# Smartcar.net
KiCad netlist of a schematic drawn in Altium Designer
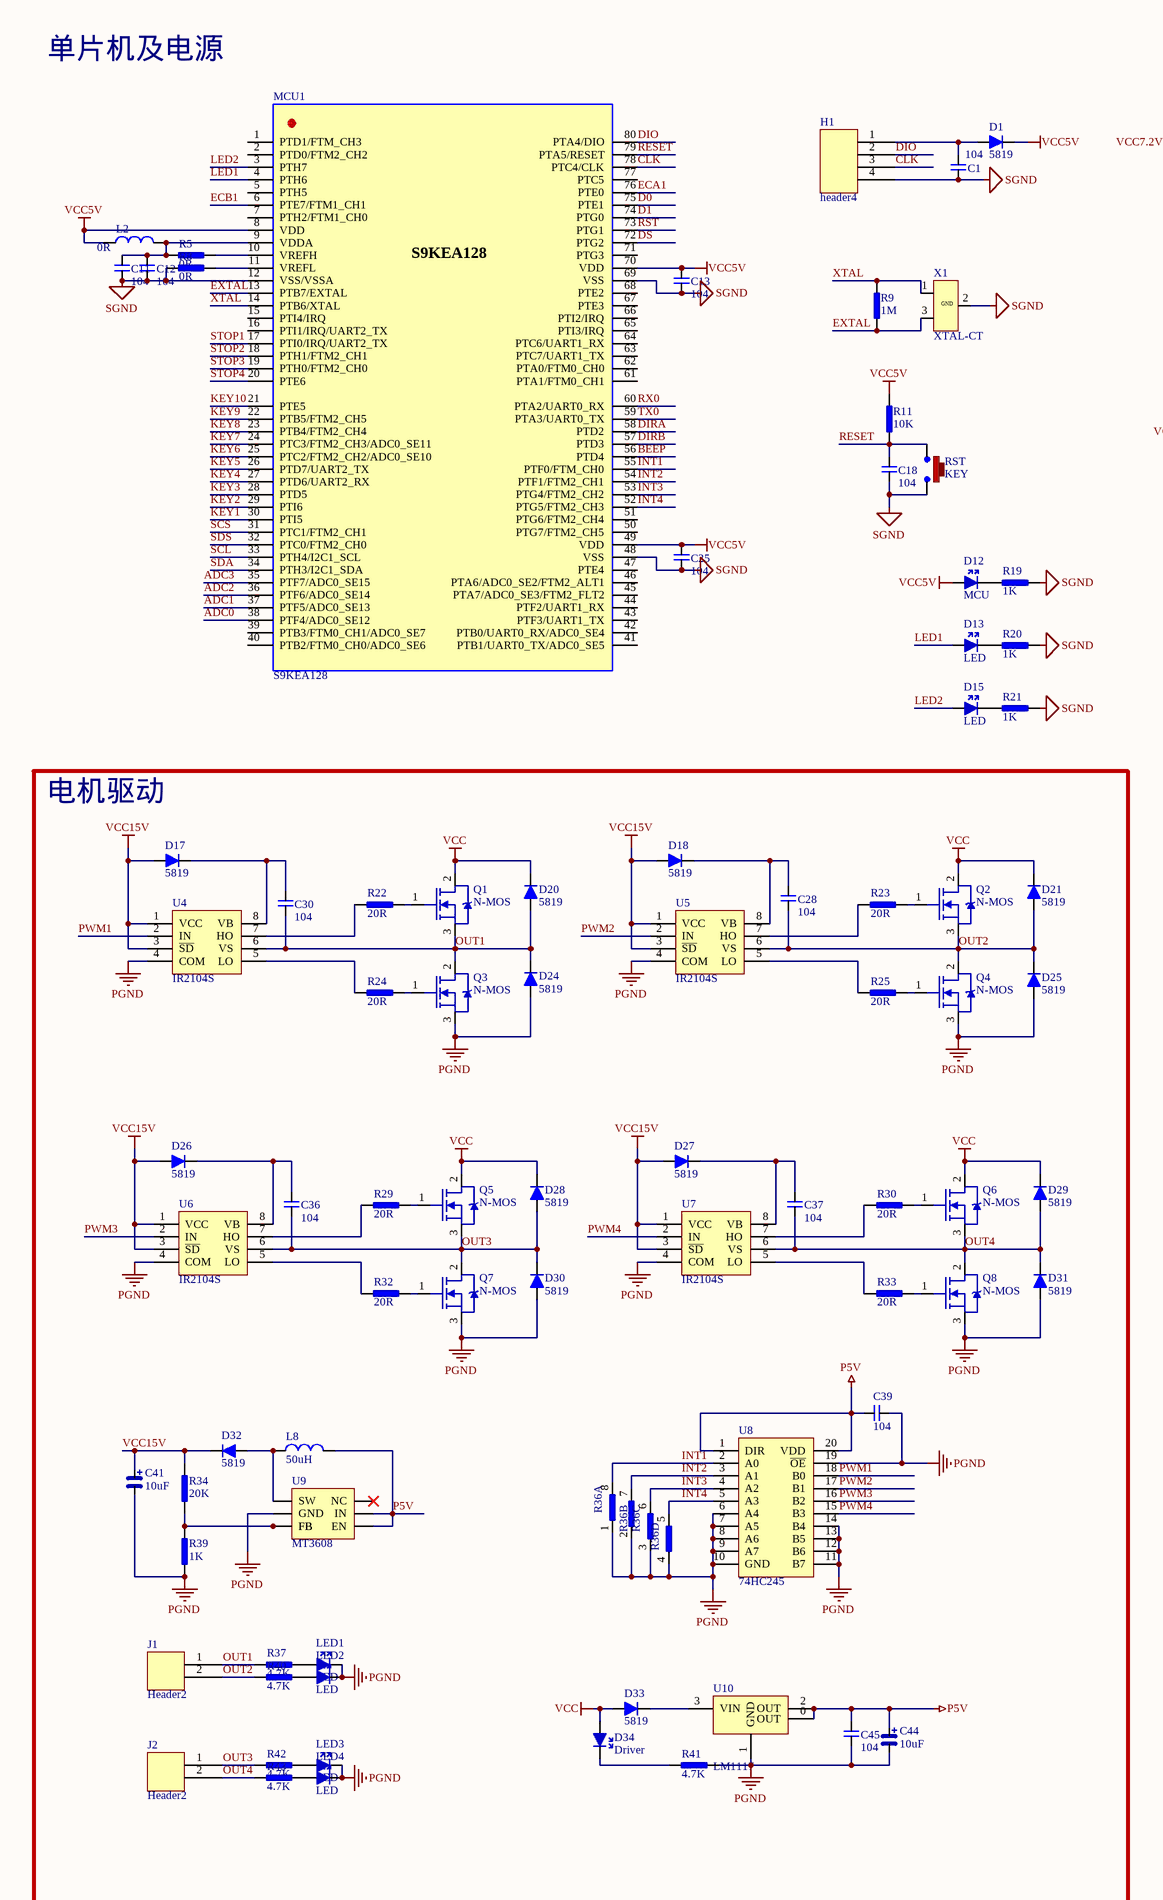
[diagram p0: Smartcar.SchDoc, left]
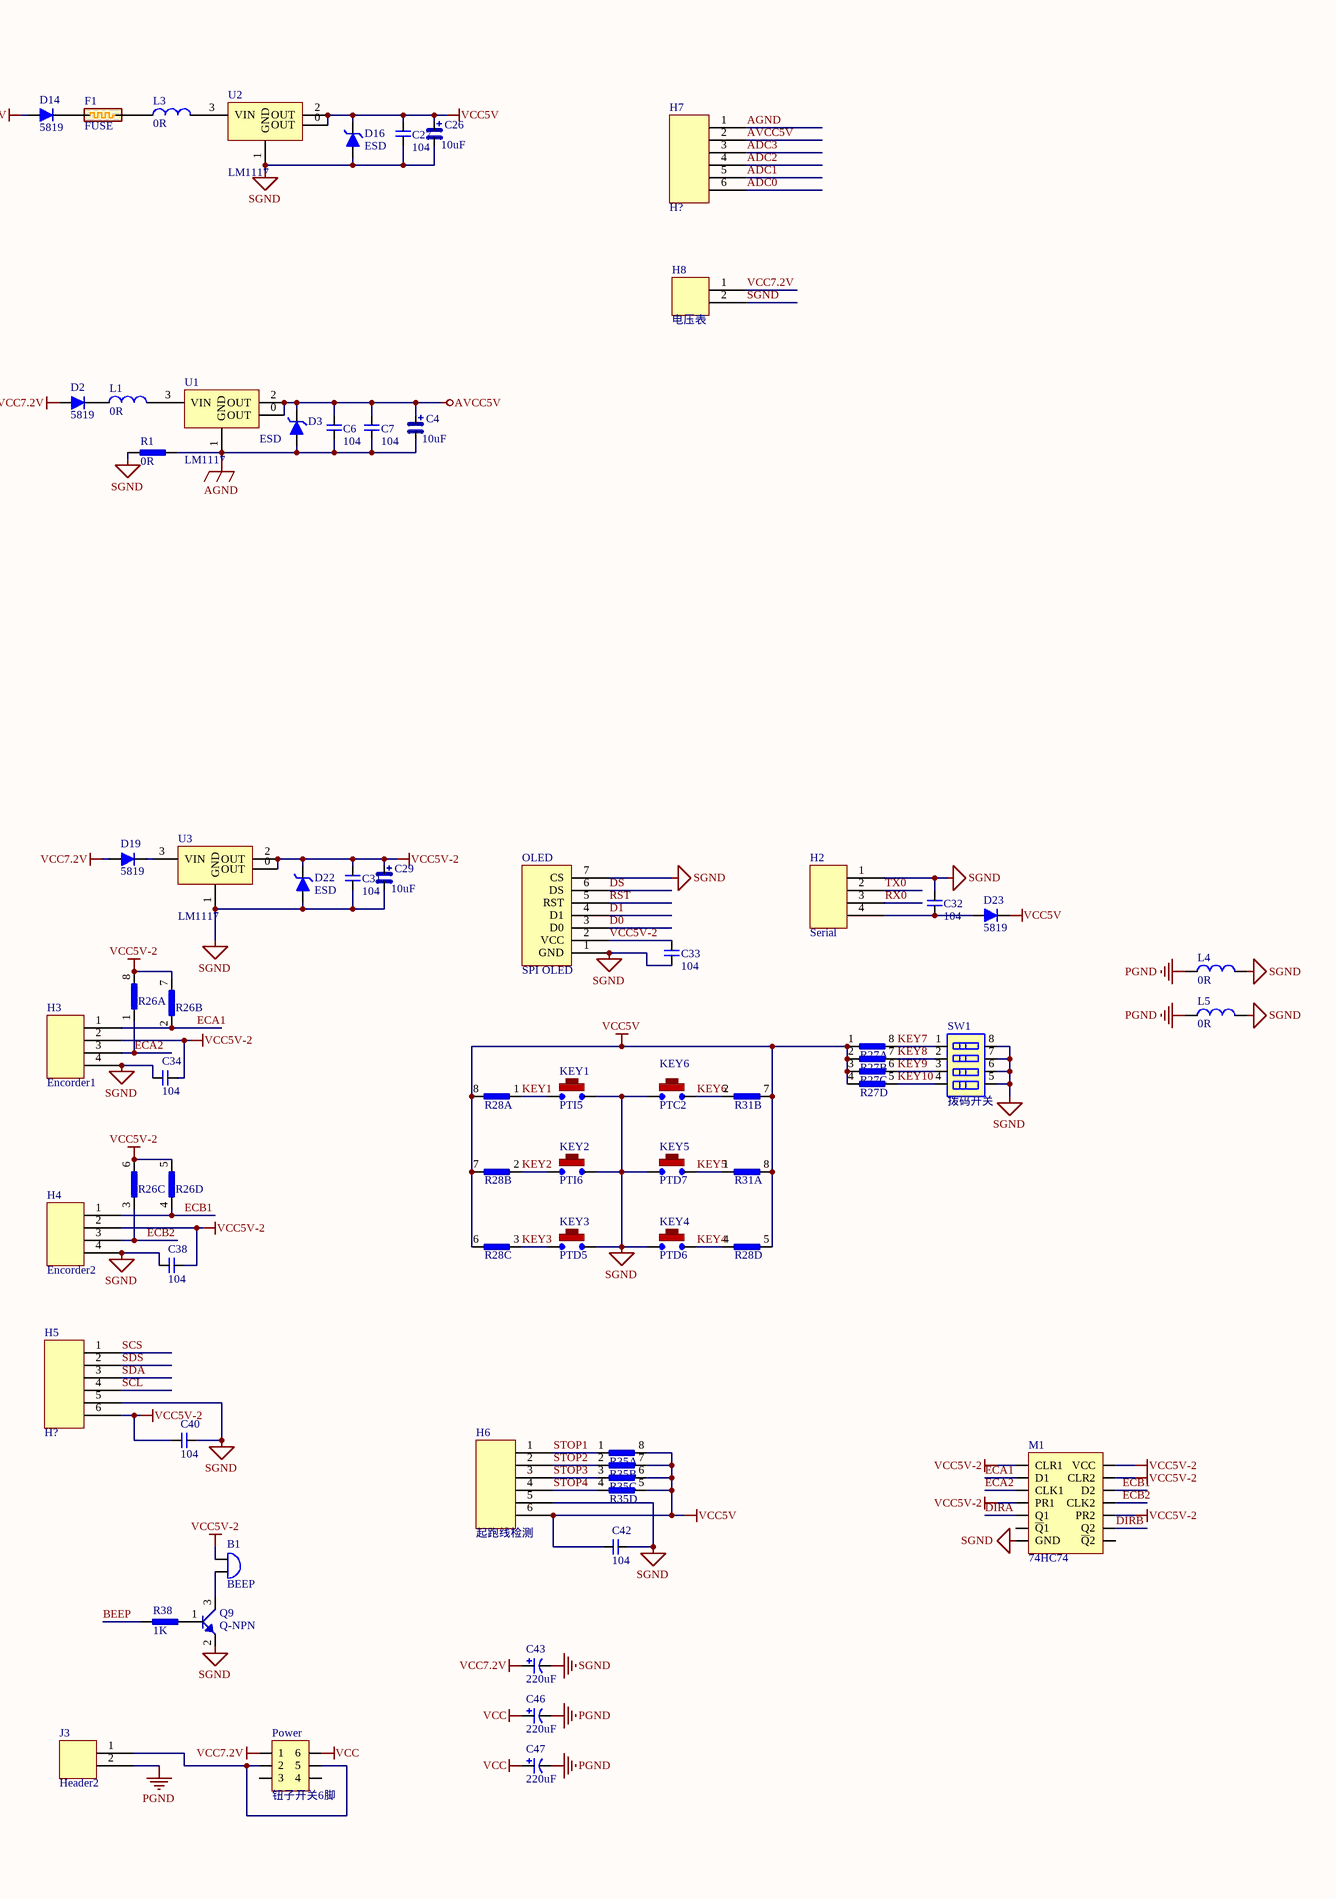
[diagram p1: Smartcar.SchDoc, right]

(export (version "E")
  (design (tool "Eeschema 10.0.6"))
  (components
    (comp (ref "B1") (value "BEEP") (footprint "BEEP") (libsource (lib "常用原理图库") (part "BEEP")))
    (comp (ref "C1") (value "104") (footprint "C0603") (libsource (lib "常用原理图库") (part "CAP")))
    (comp (ref "C4") (value "10uF") (footprint "TAN 3215") (libsource (lib "常用原理图库") (part "C-TAN")))
    (comp (ref "C6") (value "104") (footprint "C0603") (libsource (lib "常用原理图库") (part "CAP")))
    (comp (ref "C7") (value "104") (footprint "C0603") (libsource (lib "常用原理图库") (part "CAP")))
    (comp (ref "C11") (value "104") (footprint "C0603") (libsource (lib "常用原理图库") (part "CAP")))
    (comp (ref "C12") (value "104") (footprint "C0603") (libsource (lib "常用原理图库") (part "CAP")))
    (comp (ref "C13") (value "104") (footprint "C0603") (libsource (lib "常用原理图库") (part "CAP")))
    (comp (ref "C18") (value "104") (footprint "C0603") (libsource (lib "常用原理图库") (part "CAP")))
    (comp (ref "C25") (value "104") (footprint "C0603") (libsource (lib "常用原理图库") (part "CAP")))
    (comp (ref "C26") (value "10uF") (footprint "TAN 3215") (libsource (lib "常用原理图库") (part "C-TAN")))
    (comp (ref "C27") (value "104") (footprint "C0603") (libsource (lib "常用原理图库") (part "CAP")))
    (comp (ref "C28") (value "104") (footprint "C0603") (libsource (lib "常用原理图库") (part "CAP")))
    (comp (ref "C29") (value "10uF") (footprint "TAN 3215") (libsource (lib "常用原理图库") (part "C-TAN")))
    (comp (ref "C30") (value "104") (footprint "C0603") (libsource (lib "常用原理图库") (part "CAP")))
    (comp (ref "C31") (value "104") (footprint "C0603") (libsource (lib "常用原理图库") (part "CAP")))
    (comp (ref "C32") (value "104") (footprint "C0603") (libsource (lib "常用原理图库") (part "CAP")))
    (comp (ref "C33") (value "104") (footprint "C0603") (libsource (lib "常用原理图库") (part "CAP")))
    (comp (ref "C34") (value "104") (footprint "C0603") (libsource (lib "常用原理图库") (part "CAP")))
    (comp (ref "C36") (value "104") (footprint "C0603") (libsource (lib "常用原理图库") (part "CAP")))
    (comp (ref "C37") (value "104") (footprint "C0603") (libsource (lib "常用原理图库") (part "CAP")))
    (comp (ref "C38") (value "104") (footprint "C0603") (libsource (lib "常用原理图库") (part "CAP")))
    (comp (ref "C39") (value "104") (footprint "C0603") (libsource (lib "常用原理图库") (part "CAP")))
    (comp (ref "C40") (value "104") (footprint "C0603") (libsource (lib "常用原理图库") (part "CAP")))
    (comp (ref "C41") (value "10uF") (footprint "TAN 3215") (libsource (lib "常用原理图库") (part "C-TAN")))
    (comp (ref "C42") (value "104") (footprint "C0603") (libsource (lib "常用原理图库") (part "CAP")))
    (comp (ref "C43") (value "220uF") (footprint "CAP6.6X6.6") (libsource (lib "常用原理图库") (part "CAP-SMD")))
    (comp (ref "C44") (value "10uF") (footprint "TAN 3215") (libsource (lib "常用原理图库") (part "C-TAN")))
    (comp (ref "C45") (value "104") (footprint "C0603") (libsource (lib "常用原理图库") (part "CAP")))
    (comp (ref "C46") (value "220uF") (footprint "CAP6.6X6.6") (libsource (lib "常用原理图库") (part "CAP-SMD")))
    (comp (ref "C47") (value "220uF") (footprint "CAP6.6X6.6") (libsource (lib "常用原理图库") (part "CAP-SMD")))
    (comp (ref "D1") (value "5819") (footprint "SOD123") (libsource (lib "常用原理图库") (part "diode")))
    (comp (ref "D2") (value "5819") (footprint "SOD123") (libsource (lib "常用原理图库") (part "diode")))
    (comp (ref "D3") (value "ESD") (footprint "SOD323") (libsource (lib "常用原理图库") (part "D-ESD")))
    (comp (ref "D12") (value "MCU") (footprint "0603LED") (libsource (lib "常用原理图库") (part "LED")))
    (comp (ref "D13") (value "LED") (footprint "0603LED") (libsource (lib "常用原理图库") (part "LED")))
    (comp (ref "D14") (value "5819") (footprint "SOD123") (libsource (lib "常用原理图库") (part "diode")))
    (comp (ref "D15") (value "LED") (footprint "0603LED") (libsource (lib "常用原理图库") (part "LED")))
    (comp (ref "D16") (value "ESD") (footprint "SOD323") (libsource (lib "常用原理图库") (part "D-ESD")))
    (comp (ref "D17") (value "5819") (footprint "SOD123") (libsource (lib "常用原理图库") (part "Diode")))
    (comp (ref "D18") (value "5819") (footprint "SOD123") (libsource (lib "常用原理图库") (part "Diode")))
    (comp (ref "D19") (value "5819") (footprint "SOD123") (libsource (lib "常用原理图库") (part "diode")))
    (comp (ref "D20") (value "5819") (footprint "SOD123") (libsource (lib "常用原理图库") (part "Diode")))
    (comp (ref "D21") (value "5819") (footprint "SOD123") (libsource (lib "常用原理图库") (part "Diode")))
    (comp (ref "D22") (value "ESD") (footprint "SOD323") (libsource (lib "常用原理图库") (part "D-ESD")))
    (comp (ref "D23") (value "5819") (footprint "SOD323") (libsource (lib "常用原理图库") (part "Diode")))
    (comp (ref "D24") (value "5819") (footprint "SOD123") (libsource (lib "常用原理图库") (part "Diode")))
    (comp (ref "D25") (value "5819") (footprint "SOD123") (libsource (lib "常用原理图库") (part "Diode")))
    (comp (ref "D26") (value "5819") (footprint "SOD123") (libsource (lib "常用原理图库") (part "Diode")))
    (comp (ref "D27") (value "5819") (footprint "SOD123") (libsource (lib "常用原理图库") (part "Diode")))
    (comp (ref "D28") (value "5819") (footprint "SOD123") (libsource (lib "常用原理图库") (part "Diode")))
    (comp (ref "D29") (value "5819") (footprint "SOD123") (libsource (lib "常用原理图库") (part "Diode")))
    (comp (ref "D30") (value "5819") (footprint "SOD123") (libsource (lib "常用原理图库") (part "Diode")))
    (comp (ref "D31") (value "5819") (footprint "SOD123") (libsource (lib "常用原理图库") (part "Diode")))
    (comp (ref "D32") (value "5819") (footprint "SOD123") (libsource (lib "常用原理图库") (part "Diode")))
    (comp (ref "D33") (value "5819") (footprint "SOD123") (libsource (lib "常用原理图库") (part "diode")))
    (comp (ref "D34") (value "Driver") (footprint "0603LED") (libsource (lib "常用原理图库") (part "LED")))
    (comp (ref "F1") (value "FUSE") (footprint "R 0805") (libsource (lib "常用原理图库") (part "FUSE")))
    (comp (ref "H1") (value "header4") (footprint "HDR1X4") (libsource (lib "常用原理图库") (part "header4")))
    (comp (ref "H2") (value "Serial") (footprint "HDR1X4") (libsource (lib "常用原理图库") (part "header4")))
    (comp (ref "H3")
      (value "Encorder1")
      (footprint "1.25mm卧贴-4P")
      (libsource (lib "常用原理图库") (part "header4"))
    )
    (comp (ref "H4")
      (value "Encorder2")
      (footprint "1.25mm卧贴-4P")
      (libsource (lib "常用原理图库") (part "header4"))
    )
    (comp (ref "H5") (value "H?") (footprint "1.25mm卧贴-6P") (libsource (lib "常用原理图库") (part "header6")))
    (comp (ref "H6") (value "起跑线检测") (footprint "1.25mm卧贴-6P") (libsource (lib "常用原理图库") (part "header6")))
    (comp (ref "H7") (value "H?") (footprint "1.25mm卧贴-6P") (libsource (lib "常用原理图库") (part "header6")))
    (comp (ref "H8") (value "电压表") (footprint "HDR1X2") (libsource (lib "常用原理图库") (part "Header2")))
    (comp (ref "J1") (value "Header2") (footprint "motor-L") (libsource (lib "常用原理图库") (part "Header2")))
    (comp (ref "J2") (value "Header2") (footprint "MOTOR-R") (libsource (lib "常用原理图库") (part "Header2")))
    (comp (ref "J3") (value "Header2") (footprint "POWER-IN") (libsource (lib "常用原理图库") (part "Header2")))
    (comp (ref "KEY1") (value "PTI5") (footprint "轻触开关贴片") (libsource (lib "常用原理图库") (part "KEY")))
    (comp (ref "KEY2") (value "PTI6") (footprint "轻触开关贴片") (libsource (lib "常用原理图库") (part "KEY")))
    (comp (ref "KEY3") (value "PTD5") (footprint "轻触开关贴片") (libsource (lib "常用原理图库") (part "KEY")))
    (comp (ref "KEY4") (value "PTD6") (footprint "轻触开关贴片") (libsource (lib "常用原理图库") (part "KEY")))
    (comp (ref "KEY5") (value "PTD7") (footprint "轻触开关贴片") (libsource (lib "常用原理图库") (part "KEY")))
    (comp (ref "KEY6") (value "PTC2") (footprint "轻触开关贴片") (libsource (lib "常用原理图库") (part "KEY")))
    (comp (ref "L1") (value "0R") (footprint "L0603") (libsource (lib "常用原理图库") (part "Inductance")))
    (comp (ref "L2") (value "0R") (footprint "L0603") (libsource (lib "常用原理图库") (part "Inductance")))
    (comp (ref "L3") (value "0R") (footprint "L0603") (libsource (lib "常用原理图库") (part "Inductance")))
    (comp (ref "L4") (value "0R") (footprint "L0603") (libsource (lib "常用原理图库") (part "Inductance")))
    (comp (ref "L5") (value "0R") (footprint "L0603") (libsource (lib "常用原理图库") (part "Inductance")))
    (comp (ref "L8") (value "50uH") (footprint "L-06030") (libsource (lib "常用原理图库") (part "Inductance")))
    (comp (ref "LED1") (value "LED") (footprint "0603LED") (libsource (lib "常用原理图库") (part "LED")))
    (comp (ref "LED2") (value "LED") (footprint "0603LED") (libsource (lib "常用原理图库") (part "LED")))
    (comp (ref "LED3") (value "LED") (footprint "0603LED") (libsource (lib "常用原理图库") (part "LED")))
    (comp (ref "LED4") (value "LED") (footprint "0603LED") (libsource (lib "常用原理图库") (part "LED")))
    (comp (ref "M1") (value "74HC74") (footprint "ssoic14") (libsource (lib "常用原理图库") (part "74HC74")))
    (comp (ref "MCU1")
      (value "S9KEA128")
      (footprint "LQFP80-14X14")
      (libsource (lib "Smartcar") (part "S9KEA128"))
    )
    (comp (ref "OLED")
      (value "SPI OLED")
      (footprint "OLED12864")
      (libsource (lib "常用原理图库") (part "SPI OLED"))
    )
    (comp (ref "Power") (value "钮子开关6脚") (footprint "钮子开关6脚") (libsource (lib "常用原理图库") (part "钮子开关6脚")))
    (comp (ref "Q1") (value "N-MOS") (footprint "常用封装:TO-252") (libsource (lib "常用原理图库") (part "N-MOS")))
    (comp (ref "Q2") (value "N-MOS") (footprint "常用封装:TO-252") (libsource (lib "常用原理图库") (part "N-MOS")))
    (comp (ref "Q3") (value "N-MOS") (footprint "常用封装:TO-252") (libsource (lib "常用原理图库") (part "N-MOS")))
    (comp (ref "Q4") (value "N-MOS") (footprint "常用封装:TO-252") (libsource (lib "常用原理图库") (part "N-MOS")))
    (comp (ref "Q5") (value "N-MOS") (footprint "常用封装:TO-252") (libsource (lib "常用原理图库") (part "N-MOS")))
    (comp (ref "Q6") (value "N-MOS") (footprint "常用封装:TO-252") (libsource (lib "常用原理图库") (part "N-MOS")))
    (comp (ref "Q7") (value "N-MOS") (footprint "常用封装:TO-252") (libsource (lib "常用原理图库") (part "N-MOS")))
    (comp (ref "Q8") (value "N-MOS") (footprint "常用封装:TO-252") (libsource (lib "常用原理图库") (part "N-MOS")))
    (comp (ref "Q9") (value "Q-NPN") (footprint "SOT-23") (libsource (lib "常用原理图库") (part "Q-NPN")))
    (comp (ref "R1") (value "0R") (footprint "R0603") (libsource (lib "常用原理图库") (part "RES")))
    (comp (ref "R5") (value "0R") (footprint "R0603") (libsource (lib "常用原理图库") (part "RES")))
    (comp (ref "R8") (value "0R") (footprint "R0603") (libsource (lib "常用原理图库") (part "RES")))
    (comp (ref "R9") (value "1M") (footprint "R0603") (libsource (lib "") (part "RES_1")))
    (comp (ref "R11") (value "10K") (footprint "R0603") (libsource (lib "") (part "RES_2")))
    (comp (ref "R19") (value "1K") (footprint "R0603") (libsource (lib "常用原理图库") (part "RES")))
    (comp (ref "R20") (value "1K") (footprint "R0603") (libsource (lib "常用原理图库") (part "RES")))
    (comp (ref "R21") (value "1K") (footprint "R0603") (libsource (lib "常用原理图库") (part "RES")))
    (comp (ref "R22") (value "20R") (footprint "R0603") (libsource (lib "常用原理图库") (part "RES")))
    (comp (ref "R23") (value "20R") (footprint "R0603") (libsource (lib "常用原理图库") (part "RES")))
    (comp (ref "R24") (value "20R") (footprint "R0603") (libsource (lib "常用原理图库") (part "RES")))
    (comp (ref "R25") (value "20R") (footprint "R0603") (libsource (lib "常用原理图库") (part "RES")))
    (comp (ref "R26")
      (value "Res Pack-4R")
      (footprint "8P4R-0603")
      (description "排阻")
      (fields (field (name "PUBLISHER") "Altium Limited"))
      (libsource (lib "常用原理图库") (part "Res Pack-4R"))
    )
    (comp (ref "R27")
      (value "Res Pack-4R")
      (footprint "8P4R-0603")
      (description "排阻")
      (fields (field (name "PUBLISHER") "Altium Limited"))
      (libsource (lib "") (part "Res Pack-4R_1"))
    )
    (comp (ref "R28")
      (value "Res Pack-4R")
      (footprint "8P4R-0603")
      (description "排阻")
      (fields (field (name "PUBLISHER") "Altium Limited"))
      (libsource (lib "") (part "Res Pack-4R_2"))
    )
    (comp (ref "R29") (value "20R") (footprint "R0603") (libsource (lib "常用原理图库") (part "RES")))
    (comp (ref "R30") (value "20R") (footprint "R0603") (libsource (lib "常用原理图库") (part "RES")))
    (comp (ref "R31")
      (value "Res Pack-4R")
      (footprint "8P4R-0603")
      (description "排阻")
      (fields (field (name "PUBLISHER") "Altium Limited"))
      (libsource (lib "") (part "Res Pack-4R_1"))
    )
    (comp (ref "R32") (value "20R") (footprint "R0603") (libsource (lib "常用原理图库") (part "RES")))
    (comp (ref "R33") (value "20R") (footprint "R0603") (libsource (lib "常用原理图库") (part "RES")))
    (comp (ref "R34") (value "20K") (footprint "R0603") (libsource (lib "") (part "RES_1")))
    (comp (ref "R35")
      (value "10K")
      (footprint "8P4R-0603")
      (description "排阻")
      (fields (field (name "PUBLISHER") "Altium Limited"))
      (libsource (lib "") (part "Res Pack-4R_1"))
    )
    (comp (ref "R36")
      (value "Res Pack-4R")
      (footprint "8P4R-0603")
      (description "排阻")
      (fields (field (name "PUBLISHER") "Altium Limited"))
      (libsource (lib "常用原理图库") (part "Res Pack-4R"))
    )
    (comp (ref "R37") (value "4.7K") (footprint "R0603") (libsource (lib "常用原理图库") (part "RES")))
    (comp (ref "R38") (value "1K") (footprint "R0603") (libsource (lib "常用原理图库") (part "RES")))
    (comp (ref "R39") (value "1K") (footprint "R0603") (libsource (lib "") (part "RES_1")))
    (comp (ref "R40") (value "4.7K") (footprint "R0603") (libsource (lib "常用原理图库") (part "RES")))
    (comp (ref "R41") (value "4.7K") (footprint "R0603") (libsource (lib "常用原理图库") (part "RES")))
    (comp (ref "R42") (value "4.7K") (footprint "R0603") (libsource (lib "常用原理图库") (part "RES")))
    (comp (ref "R43") (value "4.7K") (footprint "R0603") (libsource (lib "常用原理图库") (part "RES")))
    (comp (ref "RST") (value "KEY") (footprint "轻触开关贴片") (libsource (lib "") (part "KEY_1")))
    (comp (ref "SW1")
      (value "拨码开关")
      (footprint "SW-DIP-4 - duplicate")
      (libsource (lib "Smartcar") (part "拨码开关"))
    )
    (comp (ref "U1") (value "LM1117") (footprint "SOT223") (libsource (lib "") (part "1117_1")))
    (comp (ref "U2") (value "LM1117") (footprint "SOT223") (libsource (lib "常用原理图库") (part "1117")))
    (comp (ref "U3") (value "LM1117") (footprint "SOT223") (libsource (lib "常用原理图库") (part "1117")))
    (comp (ref "U4")
      (value "IR2104S")
      (footprint "SOP-8")
      (description "半桥驱动器")
      (libsource (lib "MOS电机驱动") (part "IR2104S"))
    )
    (comp (ref "U5")
      (value "IR2104S")
      (footprint "SOP-8")
      (description "半桥驱动器")
      (libsource (lib "MOS电机驱动") (part "IR2104S"))
    )
    (comp (ref "U6")
      (value "IR2104S")
      (footprint "SOP-8")
      (description "半桥驱动器")
      (libsource (lib "MOS电机驱动") (part "IR2104S"))
    )
    (comp (ref "U7")
      (value "IR2104S")
      (footprint "SOP-8")
      (description "半桥驱动器")
      (libsource (lib "MOS电机驱动") (part "IR2104S"))
    )
    (comp (ref "U8") (value "74HC245") (footprint "TSSOP-20") (libsource (lib "常用原理图库") (part "74HC245")))
    (comp (ref "U9") (value "MT3608") (footprint "SOT23-6") (libsource (lib "常用原理图库") (part "MT3608")))
    (comp (ref "U10") (value "LM1117") (footprint "SOT223") (libsource (lib "常用原理图库") (part "1117")))
    (comp (ref "X1") (value "XTAL-CT") (footprint "CSTCE8M") (libsource (lib "常用原理图库") (part "XTAL-CT")))
  )
  (nets
    (net (code "1") (name "/ADC0") (class "Default")
      (node (ref "H7") (pin "6") (pintype "passive"))
      (node (ref "MCU1") (pin "38") (pinfunction "PTF4/ADC0_SE12_38") (pintype "passive"))
    )
    (net (code "2") (name "/ADC1") (class "Default")
      (node (ref "H7") (pin "5") (pintype "passive"))
      (node (ref "MCU1") (pin "37") (pinfunction "PTF5/ADC0_SE13_37") (pintype "passive"))
    )
    (net (code "3") (name "/ADC2") (class "Default")
      (node (ref "H7") (pin "4") (pintype "passive"))
      (node (ref "MCU1") (pin "36") (pinfunction "PTF6/ADC0_SE14_36") (pintype "passive"))
    )
    (net (code "4") (name "/ADC3") (class "Default")
      (node (ref "H7") (pin "3") (pintype "passive"))
      (node (ref "MCU1") (pin "35") (pinfunction "PTF7/ADC0_SE15_35") (pintype "passive"))
    )
    (net (code "5") (name "/BEEP") (class "Default")
      (node (ref "MCU1") (pin "56") (pinfunction "PTD4_56") (pintype "passive"))
      (node (ref "R38") (pin "1") (pintype "passive"))
    )
    (net (code "6") (name "/CLK") (class "Default")
      (node (ref "H1") (pin "3") (pintype "passive"))
      (node (ref "MCU1") (pin "78") (pinfunction "PTC4/CLK_78") (pintype "passive"))
    )
    (net (code "7") (name "/D0") (class "Default")
      (node (ref "MCU1") (pin "75") (pinfunction "PTE1_75") (pintype "passive"))
      (node (ref "OLED") (pin "3") (pinfunction "D0_3") (pintype "passive"))
    )
    (net (code "8") (name "/D1") (class "Default")
      (node (ref "MCU1") (pin "74") (pinfunction "PTG0_74") (pintype "passive"))
      (node (ref "OLED") (pin "4") (pinfunction "D1_4") (pintype "passive"))
    )
    (net (code "9") (name "/DIO") (class "Default")
      (node (ref "H1") (pin "2") (pintype "passive"))
      (node (ref "MCU1") (pin "80") (pinfunction "PTA4/DIO_80") (pintype "passive"))
    )
    (net (code "10") (name "/DIRA") (class "Default")
      (node (ref "M1") (pin "5") (pinfunction "Q1_5") (pintype "passive"))
      (node (ref "MCU1") (pin "58") (pinfunction "PTD2_58") (pintype "passive"))
    )
    (net (code "11") (name "/DIRB") (class "Default")
      (node (ref "M1") (pin "9") (pinfunction "Q2_9") (pintype "passive"))
      (node (ref "MCU1") (pin "57") (pinfunction "PTD3_57") (pintype "passive"))
    )
    (net (code "12") (name "/DS") (class "Default")
      (node (ref "MCU1") (pin "72") (pinfunction "PTG2_72") (pintype "passive"))
      (node (ref "OLED") (pin "6") (pinfunction "DS_6") (pintype "passive"))
    )
    (net (code "13") (name "/ECA1") (class "Default")
      (node (ref "H3") (pin "1") (pintype "passive"))
      (node (ref "M1") (pin "2") (pinfunction "D1_2") (pintype "passive"))
      (node (ref "MCU1") (pin "76") (pinfunction "PTE0_76") (pintype "passive"))
      (node (ref "R26") (pin "2") (pinfunction "2_2") (pintype "passive"))
    )
    (net (code "14") (name "/ECA2") (class "Default")
      (node (ref "H3") (pin "3") (pintype "passive"))
      (node (ref "M1") (pin "3") (pinfunction "CLK1_3") (pintype "passive"))
      (node (ref "R26") (pin "1") (pinfunction "1_1") (pintype "passive"))
    )
    (net (code "15") (name "/ECB1") (class "Default")
      (node (ref "H4") (pin "1") (pintype "passive"))
      (node (ref "M1") (pin "12") (pinfunction "D2_12") (pintype "passive"))
      (node (ref "MCU1") (pin "6") (pinfunction "PTE7/FTM1_CH1_6") (pintype "passive"))
      (node (ref "R26") (pin "4") (pinfunction "4_4") (pintype "passive"))
    )
    (net (code "16") (name "/ECB2") (class "Default")
      (node (ref "H4") (pin "3") (pintype "passive"))
      (node (ref "M1") (pin "11") (pinfunction "CLK2_11") (pintype "passive"))
      (node (ref "R26") (pin "3") (pinfunction "3_3") (pintype "passive"))
    )
    (net (code "17") (name "/EXTAL") (class "Default")
      (node (ref "MCU1") (pin "13") (pinfunction "PTB7/EXTAL_13") (pintype "passive"))
      (node (ref "R9") (pin "1") (pintype "passive"))
      (node (ref "X1") (pin "3") (pintype "passive"))
    )
    (net (code "18") (name "/INT1") (class "Default")
      (node (ref "MCU1") (pin "55") (pinfunction "PTF0/FTM_CH0_55") (pintype "passive"))
      (node (ref "R36") (pin "8") (pinfunction "8_8") (pintype "passive"))
      (node (ref "U8") (pin "2") (pinfunction "A0_2") (pintype "passive"))
    )
    (net (code "19") (name "/INT2") (class "Default")
      (node (ref "MCU1") (pin "54") (pinfunction "PTF1/FTM2_CH1_54") (pintype "passive"))
      (node (ref "R36") (pin "7") (pinfunction "7_7") (pintype "passive"))
      (node (ref "U8") (pin "3") (pinfunction "A1_3") (pintype "passive"))
    )
    (net (code "20") (name "/INT3") (class "Default")
      (node (ref "MCU1") (pin "53") (pinfunction "PTG4/FTM2_CH2_53") (pintype "passive"))
      (node (ref "R36") (pin "6") (pinfunction "6_6") (pintype "passive"))
      (node (ref "U8") (pin "4") (pinfunction "A2_4") (pintype "passive"))
    )
    (net (code "21") (name "/INT4") (class "Default")
      (node (ref "MCU1") (pin "52") (pinfunction "PTG5/FTM2_CH3_52") (pintype "passive"))
      (node (ref "R36") (pin "5") (pinfunction "5_5") (pintype "passive"))
      (node (ref "U8") (pin "5") (pinfunction "A3_5") (pintype "passive"))
    )
    (net (code "22") (name "/KEY1") (class "Default")
      (node (ref "KEY1") (pin "1") (pintype "passive"))
      (node (ref "MCU1") (pin "30") (pinfunction "PTI5_30") (pintype "passive"))
      (node (ref "R28") (pin "1") (pinfunction "1_1") (pintype "passive"))
    )
    (net (code "23") (name "/KEY2") (class "Default")
      (node (ref "KEY2") (pin "1") (pintype "passive"))
      (node (ref "MCU1") (pin "29") (pinfunction "PTI6_29") (pintype "passive"))
      (node (ref "R28") (pin "2") (pinfunction "2_2") (pintype "passive"))
    )
    (net (code "24") (name "/KEY3") (class "Default")
      (node (ref "KEY3") (pin "1") (pintype "passive"))
      (node (ref "MCU1") (pin "28") (pinfunction "PTD5_28") (pintype "passive"))
      (node (ref "R28") (pin "3") (pinfunction "3_3") (pintype "passive"))
    )
    (net (code "25") (name "/KEY4") (class "Default")
      (node (ref "KEY4") (pin "2") (pintype "passive"))
      (node (ref "MCU1") (pin "27") (pinfunction "PTD6/UART2_RX_27") (pintype "passive"))
      (node (ref "R28") (pin "4") (pinfunction "4_4") (pintype "passive"))
    )
    (net (code "26") (name "/KEY5") (class "Default")
      (node (ref "KEY5") (pin "2") (pintype "passive"))
      (node (ref "MCU1") (pin "26") (pinfunction "PTD7/UART2_TX_26") (pintype "passive"))
      (node (ref "R31") (pin "1") (pinfunction "1_1") (pintype "passive"))
    )
    (net (code "27") (name "/KEY6") (class "Default")
      (node (ref "KEY6") (pin "2") (pintype "passive"))
      (node (ref "MCU1") (pin "25") (pinfunction "PTC2/FTM2_CH2/ADC0_SE10_25") (pintype "passive"))
      (node (ref "R31") (pin "2") (pinfunction "2_2") (pintype "passive"))
    )
    (net (code "28") (name "/KEY7") (class "Default")
      (node (ref "MCU1") (pin "24") (pinfunction "PTC3/FTM2_CH3/ADC0_SE11_24") (pintype "passive"))
      (node (ref "R27") (pin "8") (pinfunction "8_8") (pintype "passive"))
      (node (ref "SW1") (pin "1") (pintype "passive"))
    )
    (net (code "29") (name "/KEY8") (class "Default")
      (node (ref "MCU1") (pin "23") (pinfunction "PTB4/FTM2_CH4_23") (pintype "passive"))
      (node (ref "R27") (pin "7") (pinfunction "7_7") (pintype "passive"))
      (node (ref "SW1") (pin "2") (pintype "passive"))
    )
    (net (code "30") (name "/KEY9") (class "Default")
      (node (ref "MCU1") (pin "22") (pinfunction "PTB5/FTM2_CH5_22") (pintype "passive"))
      (node (ref "R27") (pin "6") (pinfunction "6_6") (pintype "passive"))
      (node (ref "SW1") (pin "3") (pintype "passive"))
    )
    (net (code "31") (name "/KEY10") (class "Default")
      (node (ref "MCU1") (pin "21") (pinfunction "PTE5_21") (pintype "passive"))
      (node (ref "R27") (pin "5") (pinfunction "5_5") (pintype "passive"))
      (node (ref "SW1") (pin "4") (pintype "passive"))
    )
    (net (code "32") (name "/LED1") (class "Default")
      (node (ref "D13") (pin "1") (pintype "passive"))
      (node (ref "MCU1") (pin "4") (pinfunction "PTH6_4") (pintype "passive"))
    )
    (net (code "33") (name "/LED2") (class "Default")
      (node (ref "D15") (pin "1") (pintype "passive"))
      (node (ref "MCU1") (pin "3") (pinfunction "PTH7_3") (pintype "passive"))
    )
    (net (code "34") (name "/OUT1") (class "Default")
      (node (ref "C30") (pin "2") (pintype "passive"))
      (node (ref "D20") (pin "1") (pintype "passive"))
      (node (ref "D24") (pin "2") (pintype "passive"))
      (node (ref "J1") (pin "1") (pintype "passive"))
      (node (ref "Q1") (pin "3") (pintype "passive"))
      (node (ref "Q3") (pin "2") (pintype "passive"))
      (node (ref "R37") (pin "1") (pintype "passive"))
      (node (ref "U4") (pin "6") (pinfunction "VS_6") (pintype "passive"))
    )
    (net (code "35") (name "/OUT2") (class "Default")
      (node (ref "C28") (pin "2") (pintype "passive"))
      (node (ref "D21") (pin "1") (pintype "passive"))
      (node (ref "D25") (pin "2") (pintype "passive"))
      (node (ref "J1") (pin "2") (pintype "passive"))
      (node (ref "Q2") (pin "3") (pintype "passive"))
      (node (ref "Q4") (pin "2") (pintype "passive"))
      (node (ref "R40") (pin "1") (pintype "passive"))
      (node (ref "U5") (pin "6") (pinfunction "VS_6") (pintype "passive"))
    )
    (net (code "36") (name "/OUT3") (class "Default")
      (node (ref "C36") (pin "2") (pintype "passive"))
      (node (ref "D28") (pin "1") (pintype "passive"))
      (node (ref "D30") (pin "2") (pintype "passive"))
      (node (ref "J2") (pin "1") (pintype "passive"))
      (node (ref "Q5") (pin "3") (pintype "passive"))
      (node (ref "Q7") (pin "2") (pintype "passive"))
      (node (ref "R42") (pin "1") (pintype "passive"))
      (node (ref "U6") (pin "6") (pinfunction "VS_6") (pintype "passive"))
    )
    (net (code "37") (name "/OUT4") (class "Default")
      (node (ref "C37") (pin "2") (pintype "passive"))
      (node (ref "D29") (pin "1") (pintype "passive"))
      (node (ref "D31") (pin "2") (pintype "passive"))
      (node (ref "J2") (pin "2") (pintype "passive"))
      (node (ref "Q6") (pin "3") (pintype "passive"))
      (node (ref "Q8") (pin "2") (pintype "passive"))
      (node (ref "R43") (pin "1") (pintype "passive"))
      (node (ref "U7") (pin "6") (pinfunction "VS_6") (pintype "passive"))
    )
    (net (code "38") (name "/PWM1") (class "Default")
      (node (ref "U4") (pin "2") (pinfunction "IN_2") (pintype "passive"))
      (node (ref "U8") (pin "18") (pinfunction "B0_18") (pintype "passive"))
    )
    (net (code "39") (name "/PWM2") (class "Default")
      (node (ref "U5") (pin "2") (pinfunction "IN_2") (pintype "passive"))
      (node (ref "U8") (pin "17") (pinfunction "B1_17") (pintype "passive"))
    )
    (net (code "40") (name "/PWM3") (class "Default")
      (node (ref "U6") (pin "2") (pinfunction "IN_2") (pintype "passive"))
      (node (ref "U8") (pin "16") (pinfunction "B2_16") (pintype "passive"))
    )
    (net (code "41") (name "/PWM4") (class "Default")
      (node (ref "U7") (pin "2") (pinfunction "IN_2") (pintype "passive"))
      (node (ref "U8") (pin "15") (pinfunction "B3_15") (pintype "passive"))
    )
    (net (code "42") (name "/RESET") (class "Default")
      (node (ref "C18") (pin "1") (pintype "passive"))
      (node (ref "MCU1") (pin "79") (pinfunction "PTA5/RESET_79") (pintype "passive"))
      (node (ref "R11") (pin "2") (pintype "passive"))
      (node (ref "RST") (pin "1") (pintype "passive"))
    )
    (net (code "43") (name "/RST") (class "Default")
      (node (ref "MCU1") (pin "73") (pinfunction "PTG1_73") (pintype "passive"))
      (node (ref "OLED") (pin "5") (pinfunction "RST_5") (pintype "passive"))
    )
    (net (code "44") (name "/RX0") (class "Default")
      (node (ref "H2") (pin "3") (pintype "passive"))
      (node (ref "MCU1") (pin "60") (pinfunction "PTA2/UART0_RX_60") (pintype "passive"))
    )
    (net (code "45") (name "/SCL") (class "Default")
      (node (ref "H5") (pin "4") (pintype "passive"))
      (node (ref "MCU1") (pin "33") (pinfunction "PTH4/I2C1_SCL_33") (pintype "passive"))
    )
    (net (code "46") (name "/SCS") (class "Default")
      (node (ref "H5") (pin "1") (pintype "passive"))
      (node (ref "MCU1") (pin "31") (pinfunction "PTC1/FTM2_CH1_31") (pintype "passive"))
    )
    (net (code "47") (name "/SDA") (class "Default")
      (node (ref "H5") (pin "3") (pintype "passive"))
      (node (ref "MCU1") (pin "34") (pinfunction "PTH3/I2C1_SDA_34") (pintype "passive"))
    )
    (net (code "48") (name "/SDS") (class "Default")
      (node (ref "H5") (pin "2") (pintype "passive"))
      (node (ref "MCU1") (pin "32") (pinfunction "PTC0/FTM2_CH0_32") (pintype "passive"))
    )
    (net (code "49") (name "/STOP1") (class "Default")
      (node (ref "H6") (pin "1") (pintype "passive"))
      (node (ref "MCU1") (pin "17") (pinfunction "PTI0/IRQ/UART2_TX_17") (pintype "passive"))
      (node (ref "R35") (pin "1") (pinfunction "1_1") (pintype "passive"))
    )
    (net (code "50") (name "/STOP2") (class "Default")
      (node (ref "H6") (pin "2") (pintype "passive"))
      (node (ref "MCU1") (pin "18") (pinfunction "PTH1/FTM2_CH1_18") (pintype "passive"))
      (node (ref "R35") (pin "2") (pinfunction "2_2") (pintype "passive"))
    )
    (net (code "51") (name "/STOP3") (class "Default")
      (node (ref "H6") (pin "3") (pintype "passive"))
      (node (ref "MCU1") (pin "19") (pinfunction "PTH0/FTM2_CH0_19") (pintype "passive"))
      (node (ref "R35") (pin "3") (pinfunction "3_3") (pintype "passive"))
    )
    (net (code "52") (name "/STOP4") (class "Default")
      (node (ref "H6") (pin "4") (pintype "passive"))
      (node (ref "MCU1") (pin "20") (pinfunction "PTE6_20") (pintype "passive"))
      (node (ref "R35") (pin "4") (pinfunction "4_4") (pintype "passive"))
    )
    (net (code "53") (name "/TX0") (class "Default")
      (node (ref "H2") (pin "2") (pintype "passive"))
      (node (ref "MCU1") (pin "59") (pinfunction "PTA3/UART0_TX_59") (pintype "passive"))
    )
    (net (code "54") (name "/XTAL") (class "Default")
      (node (ref "MCU1") (pin "14") (pinfunction "PTB6/XTAL_14") (pintype "passive"))
      (node (ref "R9") (pin "2") (pintype "passive"))
      (node (ref "X1") (pin "1") (pintype "passive"))
    )
    (net (code "55") (name "AGND") (class "Default")
      (node (ref "C4") (pin "2") (pintype "passive"))
      (node (ref "C6") (pin "1") (pintype "passive"))
      (node (ref "C7") (pin "1") (pintype "passive"))
      (node (ref "D3") (pin "1") (pintype "passive"))
      (node (ref "H7") (pin "1") (pintype "passive"))
      (node (ref "R1") (pin "2") (pintype "passive"))
      (node (ref "U1") (pin "1") (pinfunction "GND_1") (pintype "passive"))
    )
    (net (code "56") (name "AVCC5V") (class "Default")
      (node (ref "C4") (pin "1") (pintype "passive"))
      (node (ref "C6") (pin "2") (pintype "passive"))
      (node (ref "C7") (pin "2") (pintype "passive"))
      (node (ref "D3") (pin "2") (pintype "passive"))
      (node (ref "H7") (pin "2") (pintype "passive"))
      (node (ref "U1") (pin "0") (pinfunction "OUT_0") (pintype "passive"))
      (node (ref "U1") (pin "2") (pinfunction "OUT_2") (pintype "passive"))
    )
    (net (code "57") (name "Net-(B1-Pad2)") (class "Default")
      (node (ref "B1") (pin "2") (pintype "passive"))
      (node (ref "Q9") (pin "3") (pinfunction "3_3") (pintype "passive"))
    )
    (net (code "58") (name "Net-(C1-Pad2)") (class "Default")
      (node (ref "C1") (pin "2") (pintype "passive"))
      (node (ref "D1") (pin "1") (pintype "passive"))
      (node (ref "H1") (pin "1") (pintype "passive"))
    )
    (net (code "59") (name "Net-(C32-Pad2)") (class "Default")
      (node (ref "C32") (pin "2") (pintype "passive"))
      (node (ref "D23") (pin "1") (pintype "passive"))
      (node (ref "H2") (pin "4") (pintype "passive"))
    )
    (net (code "60") (name "Net-(D2-Pad2)") (class "Default")
      (node (ref "D2") (pin "2") (pintype "passive"))
      (node (ref "L1") (pin "2") (pinfunction "2_2") (pintype "passive"))
    )
    (net (code "61") (name "Net-(D12-Pad2)") (class "Default")
      (node (ref "D12") (pin "2") (pintype "passive"))
      (node (ref "R19") (pin "1") (pintype "passive"))
    )
    (net (code "62") (name "Net-(D13-Pad2)") (class "Default")
      (node (ref "D13") (pin "2") (pintype "passive"))
      (node (ref "R20") (pin "1") (pintype "passive"))
    )
    (net (code "63") (name "Net-(D14-Pad2)") (class "Default")
      (node (ref "D14") (pin "2") (pintype "passive"))
      (node (ref "F1") (pin "1") (pintype "passive"))
    )
    (net (code "64") (name "Net-(D15-Pad2)") (class "Default")
      (node (ref "D15") (pin "2") (pintype "passive"))
      (node (ref "R21") (pin "1") (pintype "passive"))
    )
    (net (code "65") (name "Net-(D34-Pad2)") (class "Default")
      (node (ref "D34") (pin "2") (pintype "passive"))
      (node (ref "R41") (pin "1") (pintype "passive"))
    )
    (net (code "66") (name "Net-(F1-Pad2)") (class "Default")
      (node (ref "F1") (pin "2") (pintype "passive"))
      (node (ref "L3") (pin "2") (pinfunction "2_2") (pintype "passive"))
    )
    (net (code "67") (name "Net-(J3-Pad1)") (class "Default")
      (node (ref "J3") (pin "1") (pintype "passive"))
      (node (ref "Power") (pin "2") (pinfunction "2_2") (pintype "passive"))
      (node (ref "Power") (pin "5") (pinfunction "5_5") (pintype "passive"))
    )
    (net (code "68") (name "Net-(LED1-Pad1)") (class "Default")
      (node (ref "LED1") (pin "1") (pintype "passive"))
      (node (ref "R37") (pin "2") (pintype "passive"))
    )
    (net (code "69") (name "Net-(LED2-Pad1)") (class "Default")
      (node (ref "LED2") (pin "1") (pintype "passive"))
      (node (ref "R40") (pin "2") (pintype "passive"))
    )
    (net (code "70") (name "Net-(LED3-Pad1)") (class "Default")
      (node (ref "LED3") (pin "1") (pintype "passive"))
      (node (ref "R42") (pin "2") (pintype "passive"))
    )
    (net (code "71") (name "Net-(LED4-Pad1)") (class "Default")
      (node (ref "LED4") (pin "1") (pintype "passive"))
      (node (ref "R43") (pin "2") (pintype "passive"))
    )
    (net (code "72") (name "Net-(MCU1-VDDA)") (class "Default")
      (node (ref "C11") (pin "2") (pintype "passive"))
      (node (ref "C12") (pin "2") (pintype "passive"))
      (node (ref "L2") (pin "1") (pinfunction "1_1") (pintype "passive"))
      (node (ref "MCU1") (pin "9") (pinfunction "VDDA_9") (pintype "passive"))
      (node (ref "R5") (pin "1") (pintype "passive"))
    )
    (net (code "73") (name "Net-(MCU1-VREFH)") (class "Default")
      (node (ref "MCU1") (pin "10") (pinfunction "VREFH_10") (pintype "passive"))
      (node (ref "R5") (pin "2") (pintype "passive"))
    )
    (net (code "74") (name "Net-(MCU1-VREFL)") (class "Default")
      (node (ref "MCU1") (pin "11") (pinfunction "VREFL_11") (pintype "passive"))
      (node (ref "R8") (pin "2") (pintype "passive"))
    )
    (net (code "75") (name "Net-(Q1-Pad1)") (class "Default")
      (node (ref "Q1") (pin "1") (pintype "passive"))
      (node (ref "R22") (pin "2") (pintype "passive"))
    )
    (net (code "76") (name "Net-(Q2-Pad1)") (class "Default")
      (node (ref "Q2") (pin "1") (pintype "passive"))
      (node (ref "R23") (pin "2") (pintype "passive"))
    )
    (net (code "77") (name "Net-(Q3-Pad1)") (class "Default")
      (node (ref "Q3") (pin "1") (pintype "passive"))
      (node (ref "R24") (pin "2") (pintype "passive"))
    )
    (net (code "78") (name "Net-(Q4-Pad1)") (class "Default")
      (node (ref "Q4") (pin "1") (pintype "passive"))
      (node (ref "R25") (pin "2") (pintype "passive"))
    )
    (net (code "79") (name "Net-(Q5-Pad1)") (class "Default")
      (node (ref "Q5") (pin "1") (pintype "passive"))
      (node (ref "R29") (pin "2") (pintype "passive"))
    )
    (net (code "80") (name "Net-(Q6-Pad1)") (class "Default")
      (node (ref "Q6") (pin "1") (pintype "passive"))
      (node (ref "R30") (pin "2") (pintype "passive"))
    )
    (net (code "81") (name "Net-(Q7-Pad1)") (class "Default")
      (node (ref "Q7") (pin "1") (pintype "passive"))
      (node (ref "R32") (pin "2") (pintype "passive"))
    )
    (net (code "82") (name "Net-(Q8-Pad1)") (class "Default")
      (node (ref "Q8") (pin "1") (pintype "passive"))
      (node (ref "R33") (pin "2") (pintype "passive"))
    )
    (net (code "83") (name "Net-(Q9-Pad1)") (class "Default")
      (node (ref "Q9") (pin "1") (pinfunction "1_1") (pintype "passive"))
      (node (ref "R38") (pin "2") (pintype "passive"))
    )
    (net (code "84") (name "Net-(U1-VIN)") (class "Default")
      (node (ref "L1") (pin "1") (pinfunction "1_1") (pintype "passive"))
      (node (ref "U1") (pin "3") (pinfunction "VIN_3") (pintype "passive"))
    )
    (net (code "85") (name "Net-(U2-VIN)") (class "Default")
      (node (ref "L3") (pin "1") (pinfunction "1_1") (pintype "passive"))
      (node (ref "U2") (pin "3") (pinfunction "VIN_3") (pintype "passive"))
    )
    (net (code "86") (name "Net-(U3-VIN)") (class "Default")
      (node (ref "D19") (pin "2") (pintype "passive"))
      (node (ref "U3") (pin "3") (pinfunction "VIN_3") (pintype "passive"))
    )
    (net (code "87") (name "Net-(U4-HO)") (class "Default")
      (node (ref "R22") (pin "1") (pintype "passive"))
      (node (ref "U4") (pin "7") (pinfunction "HO_7") (pintype "passive"))
    )
    (net (code "88") (name "Net-(U4-LO)") (class "Default")
      (node (ref "R24") (pin "1") (pintype "passive"))
      (node (ref "U4") (pin "5") (pinfunction "LO_5") (pintype "passive"))
    )
    (net (code "89") (name "Net-(U4-VB)") (class "Default")
      (node (ref "C30") (pin "1") (pintype "passive"))
      (node (ref "D17") (pin "2") (pintype "passive"))
      (node (ref "U4") (pin "8") (pinfunction "VB_8") (pintype "passive"))
    )
    (net (code "90") (name "Net-(U5-HO)") (class "Default")
      (node (ref "R23") (pin "1") (pintype "passive"))
      (node (ref "U5") (pin "7") (pinfunction "HO_7") (pintype "passive"))
    )
    (net (code "91") (name "Net-(U5-LO)") (class "Default")
      (node (ref "R25") (pin "1") (pintype "passive"))
      (node (ref "U5") (pin "5") (pinfunction "LO_5") (pintype "passive"))
    )
    (net (code "92") (name "Net-(U5-VB)") (class "Default")
      (node (ref "C28") (pin "1") (pintype "passive"))
      (node (ref "D18") (pin "2") (pintype "passive"))
      (node (ref "U5") (pin "8") (pinfunction "VB_8") (pintype "passive"))
    )
    (net (code "93") (name "Net-(U6-HO)") (class "Default")
      (node (ref "R29") (pin "1") (pintype "passive"))
      (node (ref "U6") (pin "7") (pinfunction "HO_7") (pintype "passive"))
    )
    (net (code "94") (name "Net-(U6-LO)") (class "Default")
      (node (ref "R32") (pin "1") (pintype "passive"))
      (node (ref "U6") (pin "5") (pinfunction "LO_5") (pintype "passive"))
    )
    (net (code "95") (name "Net-(U6-VB)") (class "Default")
      (node (ref "C36") (pin "1") (pintype "passive"))
      (node (ref "D26") (pin "2") (pintype "passive"))
      (node (ref "U6") (pin "8") (pinfunction "VB_8") (pintype "passive"))
    )
    (net (code "96") (name "Net-(U7-HO)") (class "Default")
      (node (ref "R30") (pin "1") (pintype "passive"))
      (node (ref "U7") (pin "7") (pinfunction "HO_7") (pintype "passive"))
    )
    (net (code "97") (name "Net-(U7-LO)") (class "Default")
      (node (ref "R33") (pin "1") (pintype "passive"))
      (node (ref "U7") (pin "5") (pinfunction "LO_5") (pintype "passive"))
    )
    (net (code "98") (name "Net-(U7-VB)") (class "Default")
      (node (ref "C37") (pin "1") (pintype "passive"))
      (node (ref "D27") (pin "2") (pintype "passive"))
      (node (ref "U7") (pin "8") (pinfunction "VB_8") (pintype "passive"))
    )
    (net (code "99") (name "Net-(U9-FB)") (class "Default")
      (node (ref "R34") (pin "1") (pintype "passive"))
      (node (ref "R39") (pin "2") (pintype "passive"))
      (node (ref "U9") (pin "3") (pinfunction "FB_3") (pintype "passive"))
    )
    (net (code "100") (name "Net-(U9-SW)") (class "Default")
      (node (ref "D32") (pin "1") (pintype "passive"))
      (node (ref "L8") (pin "2") (pinfunction "2_2") (pintype "passive"))
      (node (ref "U9") (pin "1") (pinfunction "SW_1") (pintype "passive"))
    )
    (net (code "101") (name "Net-(U10-VIN)") (class "Default")
      (node (ref "D33") (pin "2") (pintype "passive"))
      (node (ref "U10") (pin "3") (pinfunction "VIN_3") (pintype "passive"))
    )
    (net (code "102") (name "P5V") (class "Default")
      (node (ref "C39") (pin "1") (pintype "passive"))
      (node (ref "C44") (pin "1") (pintype "passive"))
      (node (ref "C45") (pin "2") (pintype "passive"))
      (node (ref "L8") (pin "1") (pinfunction "1_1") (pintype "passive"))
      (node (ref "U10") (pin "0") (pinfunction "OUT_0") (pintype "passive"))
      (node (ref "U10") (pin "2") (pinfunction "OUT_2") (pintype "passive"))
      (node (ref "U8") (pin "1") (pinfunction "DIR_1") (pintype "passive"))
      (node (ref "U8") (pin "20") (pinfunction "VDD_20") (pintype "passive"))
      (node (ref "U9") (pin "4") (pinfunction "EN_4") (pintype "passive"))
      (node (ref "U9") (pin "5") (pinfunction "IN_5") (pintype "passive"))
    )
    (net (code "103") (name "PGND") (class "Default")
      (node (ref "C39") (pin "2") (pintype "passive"))
      (node (ref "C41") (pin "2") (pintype "passive"))
      (node (ref "C44") (pin "2") (pintype "passive"))
      (node (ref "C45") (pin "1") (pintype "passive"))
      (node (ref "C46") (pin "1") (pintype "passive"))
      (node (ref "C47") (pin "1") (pintype "passive"))
      (node (ref "D24") (pin "1") (pintype "passive"))
      (node (ref "D25") (pin "1") (pintype "passive"))
      (node (ref "D30") (pin "1") (pintype "passive"))
      (node (ref "D31") (pin "1") (pintype "passive"))
      (node (ref "J3") (pin "2") (pintype "passive"))
      (node (ref "L4") (pin "2") (pinfunction "2_2") (pintype "passive"))
      (node (ref "L5") (pin "2") (pinfunction "2_2") (pintype "passive"))
      (node (ref "LED1") (pin "2") (pintype "passive"))
      (node (ref "LED2") (pin "2") (pintype "passive"))
      (node (ref "LED3") (pin "2") (pintype "passive"))
      (node (ref "LED4") (pin "2") (pintype "passive"))
      (node (ref "Q3") (pin "3") (pintype "passive"))
      (node (ref "Q4") (pin "3") (pintype "passive"))
      (node (ref "Q7") (pin "3") (pintype "passive"))
      (node (ref "Q8") (pin "3") (pintype "passive"))
      (node (ref "R36") (pin "1") (pinfunction "1_1") (pintype "passive"))
      (node (ref "R36") (pin "2") (pinfunction "2_2") (pintype "passive"))
      (node (ref "R36") (pin "3") (pinfunction "3_3") (pintype "passive"))
      (node (ref "R36") (pin "4") (pinfunction "4_4") (pintype "passive"))
      (node (ref "R39") (pin "1") (pintype "passive"))
      (node (ref "R41") (pin "2") (pintype "passive"))
      (node (ref "U10") (pin "1") (pinfunction "GND_1") (pintype "passive"))
      (node (ref "U4") (pin "4") (pinfunction "COM_4") (pintype "passive"))
      (node (ref "U5") (pin "4") (pinfunction "COM_4") (pintype "passive"))
      (node (ref "U6") (pin "4") (pinfunction "COM_4") (pintype "passive"))
      (node (ref "U7") (pin "4") (pinfunction "COM_4") (pintype "passive"))
      (node (ref "U8") (pin "10") (pinfunction "GND_10") (pintype "passive"))
      (node (ref "U8") (pin "11") (pinfunction "B7_11") (pintype "passive"))
      (node (ref "U8") (pin "12") (pinfunction "B6_12") (pintype "passive"))
      (node (ref "U8") (pin "13") (pinfunction "B5_13") (pintype "passive"))
      (node (ref "U8") (pin "14") (pinfunction "B4_14") (pintype "passive"))
      (node (ref "U8") (pin "19") (pinfunction "~{OE}_19") (pintype "passive"))
      (node (ref "U8") (pin "6") (pinfunction "A4_6") (pintype "passive"))
      (node (ref "U8") (pin "7") (pinfunction "A5_7") (pintype "passive"))
      (node (ref "U8") (pin "8") (pinfunction "A6_8") (pintype "passive"))
      (node (ref "U8") (pin "9") (pinfunction "A7_9") (pintype "passive"))
      (node (ref "U9") (pin "2") (pinfunction "GND_2") (pintype "passive"))
    )
    (net (code "104") (name "SGND") (class "Default")
      (node (ref "C1") (pin "1") (pintype "passive"))
      (node (ref "C11") (pin "1") (pintype "passive"))
      (node (ref "C12") (pin "1") (pintype "passive"))
      (node (ref "C13") (pin "1") (pintype "passive"))
      (node (ref "C18") (pin "2") (pintype "passive"))
      (node (ref "C25") (pin "1") (pintype "passive"))
      (node (ref "C26") (pin "2") (pintype "passive"))
      (node (ref "C27") (pin "1") (pintype "passive"))
      (node (ref "C29") (pin "2") (pintype "passive"))
      (node (ref "C31") (pin "1") (pintype "passive"))
      (node (ref "C32") (pin "1") (pintype "passive"))
      (node (ref "C33") (pin "1") (pintype "passive"))
      (node (ref "C34") (pin "1") (pintype "passive"))
      (node (ref "C38") (pin "1") (pintype "passive"))
      (node (ref "C40") (pin "2") (pintype "passive"))
      (node (ref "C42") (pin "2") (pintype "passive"))
      (node (ref "C43") (pin "1") (pintype "passive"))
      (node (ref "D16") (pin "1") (pintype "passive"))
      (node (ref "D22") (pin "1") (pintype "passive"))
      (node (ref "H1") (pin "4") (pintype "passive"))
      (node (ref "H2") (pin "1") (pintype "passive"))
      (node (ref "H3") (pin "4") (pintype "passive"))
      (node (ref "H4") (pin "4") (pintype "passive"))
      (node (ref "H5") (pin "5") (pintype "passive"))
      (node (ref "H6") (pin "5") (pintype "passive"))
      (node (ref "H8") (pin "2") (pintype "passive"))
      (node (ref "KEY1") (pin "2") (pintype "passive"))
      (node (ref "KEY2") (pin "2") (pintype "passive"))
      (node (ref "KEY3") (pin "2") (pintype "passive"))
      (node (ref "KEY4") (pin "1") (pintype "passive"))
      (node (ref "KEY5") (pin "1") (pintype "passive"))
      (node (ref "KEY6") (pin "1") (pintype "passive"))
      (node (ref "L4") (pin "1") (pinfunction "1_1") (pintype "passive"))
      (node (ref "L5") (pin "1") (pinfunction "1_1") (pintype "passive"))
      (node (ref "M1") (pin "7") (pinfunction "GND_7") (pintype "passive"))
      (node (ref "MCU1") (pin "12") (pinfunction "VSS/VSSA_12") (pintype "passive"))
      (node (ref "MCU1") (pin "48") (pinfunction "VSS_48") (pintype "passive"))
      (node (ref "MCU1") (pin "69") (pinfunction "VSS_69") (pintype "passive"))
      (node (ref "OLED") (pin "1") (pinfunction "GND_1") (pintype "passive"))
      (node (ref "OLED") (pin "7") (pinfunction "CS_7") (pintype "passive"))
      (node (ref "Q9") (pin "2") (pinfunction "2_2") (pintype "passive"))
      (node (ref "R1") (pin "1") (pintype "passive"))
      (node (ref "R19") (pin "2") (pintype "passive"))
      (node (ref "R20") (pin "2") (pintype "passive"))
      (node (ref "R21") (pin "2") (pintype "passive"))
      (node (ref "R8") (pin "1") (pintype "passive"))
      (node (ref "RST") (pin "2") (pintype "passive"))
      (node (ref "SW1") (pin "5") (pintype "passive"))
      (node (ref "SW1") (pin "6") (pintype "passive"))
      (node (ref "SW1") (pin "7") (pintype "passive"))
      (node (ref "SW1") (pin "8") (pintype "passive"))
      (node (ref "U2") (pin "1") (pinfunction "GND_1") (pintype "passive"))
      (node (ref "U3") (pin "1") (pinfunction "GND_1") (pintype "passive"))
      (node (ref "X1") (pin "2") (pinfunction "GND_2") (pintype "passive"))
    )
    (net (code "105") (name "VCC") (class "Default")
      (node (ref "C46") (pin "2") (pintype "passive"))
      (node (ref "C47") (pin "2") (pintype "passive"))
      (node (ref "D20") (pin "2") (pintype "passive"))
      (node (ref "D21") (pin "2") (pintype "passive"))
      (node (ref "D28") (pin "2") (pintype "passive"))
      (node (ref "D29") (pin "2") (pintype "passive"))
      (node (ref "D33") (pin "1") (pintype "passive"))
      (node (ref "D34") (pin "1") (pintype "passive"))
      (node (ref "Power") (pin "6") (pinfunction "6_6") (pintype "passive"))
      (node (ref "Q1") (pin "2") (pintype "passive"))
      (node (ref "Q2") (pin "2") (pintype "passive"))
      (node (ref "Q5") (pin "2") (pintype "passive"))
      (node (ref "Q6") (pin "2") (pintype "passive"))
    )
    (net (code "106") (name "VCC5V") (class "Default")
      (node (ref "C13") (pin "2") (pintype "passive"))
      (node (ref "C25") (pin "2") (pintype "passive"))
      (node (ref "C26") (pin "1") (pintype "passive"))
      (node (ref "C27") (pin "2") (pintype "passive"))
      (node (ref "C42") (pin "1") (pintype "passive"))
      (node (ref "D1") (pin "2") (pintype "passive"))
      (node (ref "D12") (pin "1") (pintype "passive"))
      (node (ref "D16") (pin "2") (pintype "passive"))
      (node (ref "D23") (pin "2") (pintype "passive"))
      (node (ref "H6") (pin "6") (pintype "passive"))
      (node (ref "L2") (pin "2") (pinfunction "2_2") (pintype "passive"))
      (node (ref "MCU1") (pin "49") (pinfunction "VDD_49") (pintype "passive"))
      (node (ref "MCU1") (pin "70") (pinfunction "VDD_70") (pintype "passive"))
      (node (ref "MCU1") (pin "8") (pinfunction "VDD_8") (pintype "passive"))
      (node (ref "R11") (pin "1") (pintype "passive"))
      (node (ref "R27") (pin "1") (pinfunction "1_1") (pintype "passive"))
      (node (ref "R27") (pin "2") (pinfunction "2_2") (pintype "passive"))
      (node (ref "R27") (pin "3") (pinfunction "3_3") (pintype "passive"))
      (node (ref "R27") (pin "4") (pinfunction "4_4") (pintype "passive"))
      (node (ref "R28") (pin "5") (pinfunction "5_5") (pintype "passive"))
      (node (ref "R28") (pin "6") (pinfunction "6_6") (pintype "passive"))
      (node (ref "R28") (pin "7") (pinfunction "7_7") (pintype "passive"))
      (node (ref "R28") (pin "8") (pinfunction "8_8") (pintype "passive"))
      (node (ref "R31") (pin "7") (pinfunction "7_7") (pintype "passive"))
      (node (ref "R31") (pin "8") (pinfunction "8_8") (pintype "passive"))
      (node (ref "R35") (pin "5") (pinfunction "5_5") (pintype "passive"))
      (node (ref "R35") (pin "6") (pinfunction "6_6") (pintype "passive"))
      (node (ref "R35") (pin "7") (pinfunction "7_7") (pintype "passive"))
      (node (ref "R35") (pin "8") (pinfunction "8_8") (pintype "passive"))
      (node (ref "U2") (pin "0") (pinfunction "OUT_0") (pintype "passive"))
      (node (ref "U2") (pin "2") (pinfunction "OUT_2") (pintype "passive"))
    )
    (net (code "107") (name "VCC5V-2") (class "Default")
      (node (ref "B1") (pin "1") (pintype "passive"))
      (node (ref "C29") (pin "1") (pintype "passive"))
      (node (ref "C31") (pin "2") (pintype "passive"))
      (node (ref "C33") (pin "2") (pintype "passive"))
      (node (ref "C34") (pin "2") (pintype "passive"))
      (node (ref "C38") (pin "2") (pintype "passive"))
      (node (ref "C40") (pin "1") (pintype "passive"))
      (node (ref "D22") (pin "2") (pintype "passive"))
      (node (ref "H3") (pin "2") (pintype "passive"))
      (node (ref "H4") (pin "2") (pintype "passive"))
      (node (ref "H5") (pin "6") (pintype "passive"))
      (node (ref "M1") (pin "1") (pinfunction "CLR1_1") (pintype "passive"))
      (node (ref "M1") (pin "10") (pinfunction "PR2_10") (pintype "passive"))
      (node (ref "M1") (pin "13") (pinfunction "CLR2_13") (pintype "passive"))
      (node (ref "M1") (pin "14") (pinfunction "VCC_14") (pintype "passive"))
      (node (ref "M1") (pin "4") (pinfunction "PR1_4") (pintype "passive"))
      (node (ref "OLED") (pin "2") (pinfunction "VCC_2") (pintype "passive"))
      (node (ref "R26") (pin "5") (pinfunction "5_5") (pintype "passive"))
      (node (ref "R26") (pin "6") (pinfunction "6_6") (pintype "passive"))
      (node (ref "R26") (pin "7") (pinfunction "7_7") (pintype "passive"))
      (node (ref "R26") (pin "8") (pinfunction "8_8") (pintype "passive"))
      (node (ref "U3") (pin "0") (pinfunction "OUT_0") (pintype "passive"))
      (node (ref "U3") (pin "2") (pinfunction "OUT_2") (pintype "passive"))
    )
    (net (code "108") (name "VCC7.2V") (class "Default")
      (node (ref "C43") (pin "2") (pintype "passive"))
      (node (ref "D14") (pin "1") (pintype "passive"))
      (node (ref "D19") (pin "1") (pintype "passive"))
      (node (ref "D2") (pin "1") (pintype "passive"))
      (node (ref "H8") (pin "1") (pintype "passive"))
      (node (ref "Power") (pin "1") (pinfunction "1_1") (pintype "passive"))
    )
    (net (code "109") (name "VCC15V") (class "Default")
      (node (ref "C41") (pin "1") (pintype "passive"))
      (node (ref "D17") (pin "1") (pintype "passive"))
      (node (ref "D18") (pin "1") (pintype "passive"))
      (node (ref "D26") (pin "1") (pintype "passive"))
      (node (ref "D27") (pin "1") (pintype "passive"))
      (node (ref "D32") (pin "2") (pintype "passive"))
      (node (ref "R34") (pin "2") (pintype "passive"))
      (node (ref "U4") (pin "1") (pinfunction "VCC_1") (pintype "passive"))
      (node (ref "U4") (pin "3") (pinfunction "~{SD}_3") (pintype "passive"))
      (node (ref "U5") (pin "1") (pinfunction "VCC_1") (pintype "passive"))
      (node (ref "U5") (pin "3") (pinfunction "~{SD}_3") (pintype "passive"))
      (node (ref "U6") (pin "1") (pinfunction "VCC_1") (pintype "passive"))
      (node (ref "U6") (pin "3") (pinfunction "~{SD}_3") (pintype "passive"))
      (node (ref "U7") (pin "1") (pinfunction "VCC_1") (pintype "passive"))
      (node (ref "U7") (pin "3") (pinfunction "~{SD}_3") (pintype "passive"))
    )
    (net (code "110") (name "unconnected-(M1-~{Q}1-Pad6)") (class "Default")
      (node (ref "M1") (pin "6") (pinfunction "~{Q}1_6") (pintype "passive"))
    )
    (net (code "111") (name "unconnected-(M1-~{Q}2-Pad8)") (class "Default")
      (node (ref "M1") (pin "8") (pinfunction "~{Q}2_8") (pintype "passive"))
    )
    (net (code "112") (name "unconnected-(MCU1-PTA0{slash}FTM0_CH0-Pad62)") (class "Default")
      (node (ref "MCU1") (pin "62") (pinfunction "PTA0/FTM0_CH0_62") (pintype "passive"))
    )
    (net (code "113") (name "unconnected-(MCU1-PTA1{slash}FTM0_CH1-Pad61)") (class "Default")
      (node (ref "MCU1") (pin "61") (pinfunction "PTA1/FTM0_CH1_61") (pintype "passive"))
    )
    (net (code "114") (name "unconnected-(MCU1-PTA6{slash}ADC0_SE2{slash}FTM2_ALT1-Pad46)") (class "Default")
      (node (ref "MCU1") (pin "46") (pinfunction "PTA6/ADC0_SE2/FTM2_ALT1_46") (pintype "passive"))
    )
    (net (code "115") (name "unconnected-(MCU1-PTA7{slash}ADC0_SE3{slash}FTM2_FLT2-Pad45)") (class "Default")
      (node (ref "MCU1") (pin "45") (pinfunction "PTA7/ADC0_SE3/FTM2_FLT2_45") (pintype "passive"))
    )
    (net (code "116") (name "unconnected-(MCU1-PTB0{slash}UART0_RX{slash}ADC0_SE4-Pad42)") (class "Default")
      (node (ref "MCU1") (pin "42") (pinfunction "PTB0/UART0_RX/ADC0_SE4_42") (pintype "passive"))
    )
    (net (code "117") (name "unconnected-(MCU1-PTB1{slash}UART0_TX{slash}ADC0_SE5-Pad41)") (class "Default")
      (node (ref "MCU1") (pin "41") (pinfunction "PTB1/UART0_TX/ADC0_SE5_41") (pintype "passive"))
    )
    (net (code "118") (name "unconnected-(MCU1-PTB2{slash}FTM0_CH0{slash}ADC0_SE6-Pad40)") (class "Default")
      (node (ref "MCU1") (pin "40") (pinfunction "PTB2/FTM0_CH0/ADC0_SE6_40") (pintype "passive"))
    )
    (net (code "119") (name "unconnected-(MCU1-PTB3{slash}FTM0_CH1{slash}ADC0_SE7-Pad39)") (class "Default")
      (node (ref "MCU1") (pin "39") (pinfunction "PTB3/FTM0_CH1/ADC0_SE7_39") (pintype "passive"))
    )
    (net (code "120") (name "unconnected-(MCU1-PTC5-Pad77)") (class "Default")
      (node (ref "MCU1") (pin "77") (pinfunction "PTC5_77") (pintype "passive"))
    )
    (net (code "121") (name "unconnected-(MCU1-PTC6{slash}UART1_RX-Pad64)") (class "Default")
      (node (ref "MCU1") (pin "64") (pinfunction "PTC6/UART1_RX_64") (pintype "passive"))
    )
    (net (code "122") (name "unconnected-(MCU1-PTC7{slash}UART1_TX-Pad63)") (class "Default")
      (node (ref "MCU1") (pin "63") (pinfunction "PTC7/UART1_TX_63") (pintype "passive"))
    )
    (net (code "123") (name "unconnected-(MCU1-PTD0{slash}FTM2_CH2-Pad2)") (class "Default")
      (node (ref "MCU1") (pin "2") (pinfunction "PTD0/FTM2_CH2_2") (pintype "passive"))
    )
    (net (code "124") (name "unconnected-(MCU1-PTD1{slash}FTM_CH3-Pad1)") (class "Default")
      (node (ref "MCU1") (pin "1") (pinfunction "PTD1/FTM_CH3_1") (pintype "passive"))
    )
    (net (code "125") (name "unconnected-(MCU1-PTE2-Pad68)") (class "Default")
      (node (ref "MCU1") (pin "68") (pinfunction "PTE2_68") (pintype "passive"))
    )
    (net (code "126") (name "unconnected-(MCU1-PTE3-Pad67)") (class "Default")
      (node (ref "MCU1") (pin "67") (pinfunction "PTE3_67") (pintype "passive"))
    )
    (net (code "127") (name "unconnected-(MCU1-PTE4-Pad47)") (class "Default")
      (node (ref "MCU1") (pin "47") (pinfunction "PTE4_47") (pintype "passive"))
    )
    (net (code "128") (name "unconnected-(MCU1-PTF2{slash}UART1_RX-Pad44)") (class "Default")
      (node (ref "MCU1") (pin "44") (pinfunction "PTF2/UART1_RX_44") (pintype "passive"))
    )
    (net (code "129") (name "unconnected-(MCU1-PTF3{slash}UART1_TX-Pad43)") (class "Default")
      (node (ref "MCU1") (pin "43") (pinfunction "PTF3/UART1_TX_43") (pintype "passive"))
    )
    (net (code "130") (name "unconnected-(MCU1-PTG3-Pad71)") (class "Default")
      (node (ref "MCU1") (pin "71") (pinfunction "PTG3_71") (pintype "passive"))
    )
    (net (code "131") (name "unconnected-(MCU1-PTG6{slash}FTM2_CH4-Pad51)") (class "Default")
      (node (ref "MCU1") (pin "51") (pinfunction "PTG6/FTM2_CH4_51") (pintype "passive"))
    )
    (net (code "132") (name "unconnected-(MCU1-PTG7{slash}FTM2_CH5-Pad50)") (class "Default")
      (node (ref "MCU1") (pin "50") (pinfunction "PTG7/FTM2_CH5_50") (pintype "passive"))
    )
    (net (code "133") (name "unconnected-(MCU1-PTH2{slash}FTM1_CH0-Pad7)") (class "Default")
      (node (ref "MCU1") (pin "7") (pinfunction "PTH2/FTM1_CH0_7") (pintype "passive"))
    )
    (net (code "134") (name "unconnected-(MCU1-PTH5-Pad5)") (class "Default")
      (node (ref "MCU1") (pin "5") (pinfunction "PTH5_5") (pintype "passive"))
    )
    (net (code "135") (name "unconnected-(MCU1-PTI1{slash}IRQ{slash}UART2_TX-Pad16)") (class "Default")
      (node (ref "MCU1") (pin "16") (pinfunction "PTI1/IRQ/UART2_TX_16") (pintype "passive"))
    )
    (net (code "136") (name "unconnected-(MCU1-PTI2{slash}IRQ-Pad66)") (class "Default")
      (node (ref "MCU1") (pin "66") (pinfunction "PTI2/IRQ_66") (pintype "passive"))
    )
    (net (code "137") (name "unconnected-(MCU1-PTI3{slash}IRQ-Pad65)") (class "Default")
      (node (ref "MCU1") (pin "65") (pinfunction "PTI3/IRQ_65") (pintype "passive"))
    )
    (net (code "138") (name "unconnected-(MCU1-PTI4{slash}IRQ-Pad15)") (class "Default")
      (node (ref "MCU1") (pin "15") (pinfunction "PTI4/IRQ_15") (pintype "passive"))
    )
    (net (code "139") (name "unconnected-(Power-Pad3)") (class "Default")
      (node (ref "Power") (pin "3") (pinfunction "3_3") (pintype "passive"))
    )
    (net (code "140") (name "unconnected-(Power-Pad4)") (class "Default")
      (node (ref "Power") (pin "4") (pinfunction "4_4") (pintype "passive"))
    )
    (net (code "141") (name "unconnected-(U9-NC-Pad6)") (class "Default")
      (node (ref "U9") (pin "6") (pinfunction "NC_6") (pintype "passive+no_connect"))
    )
  )
)
